# SCH_DINKI-BLINKI_2026-10-03_1.net
KiCad netlist of a schematic drawn in EasyEDA
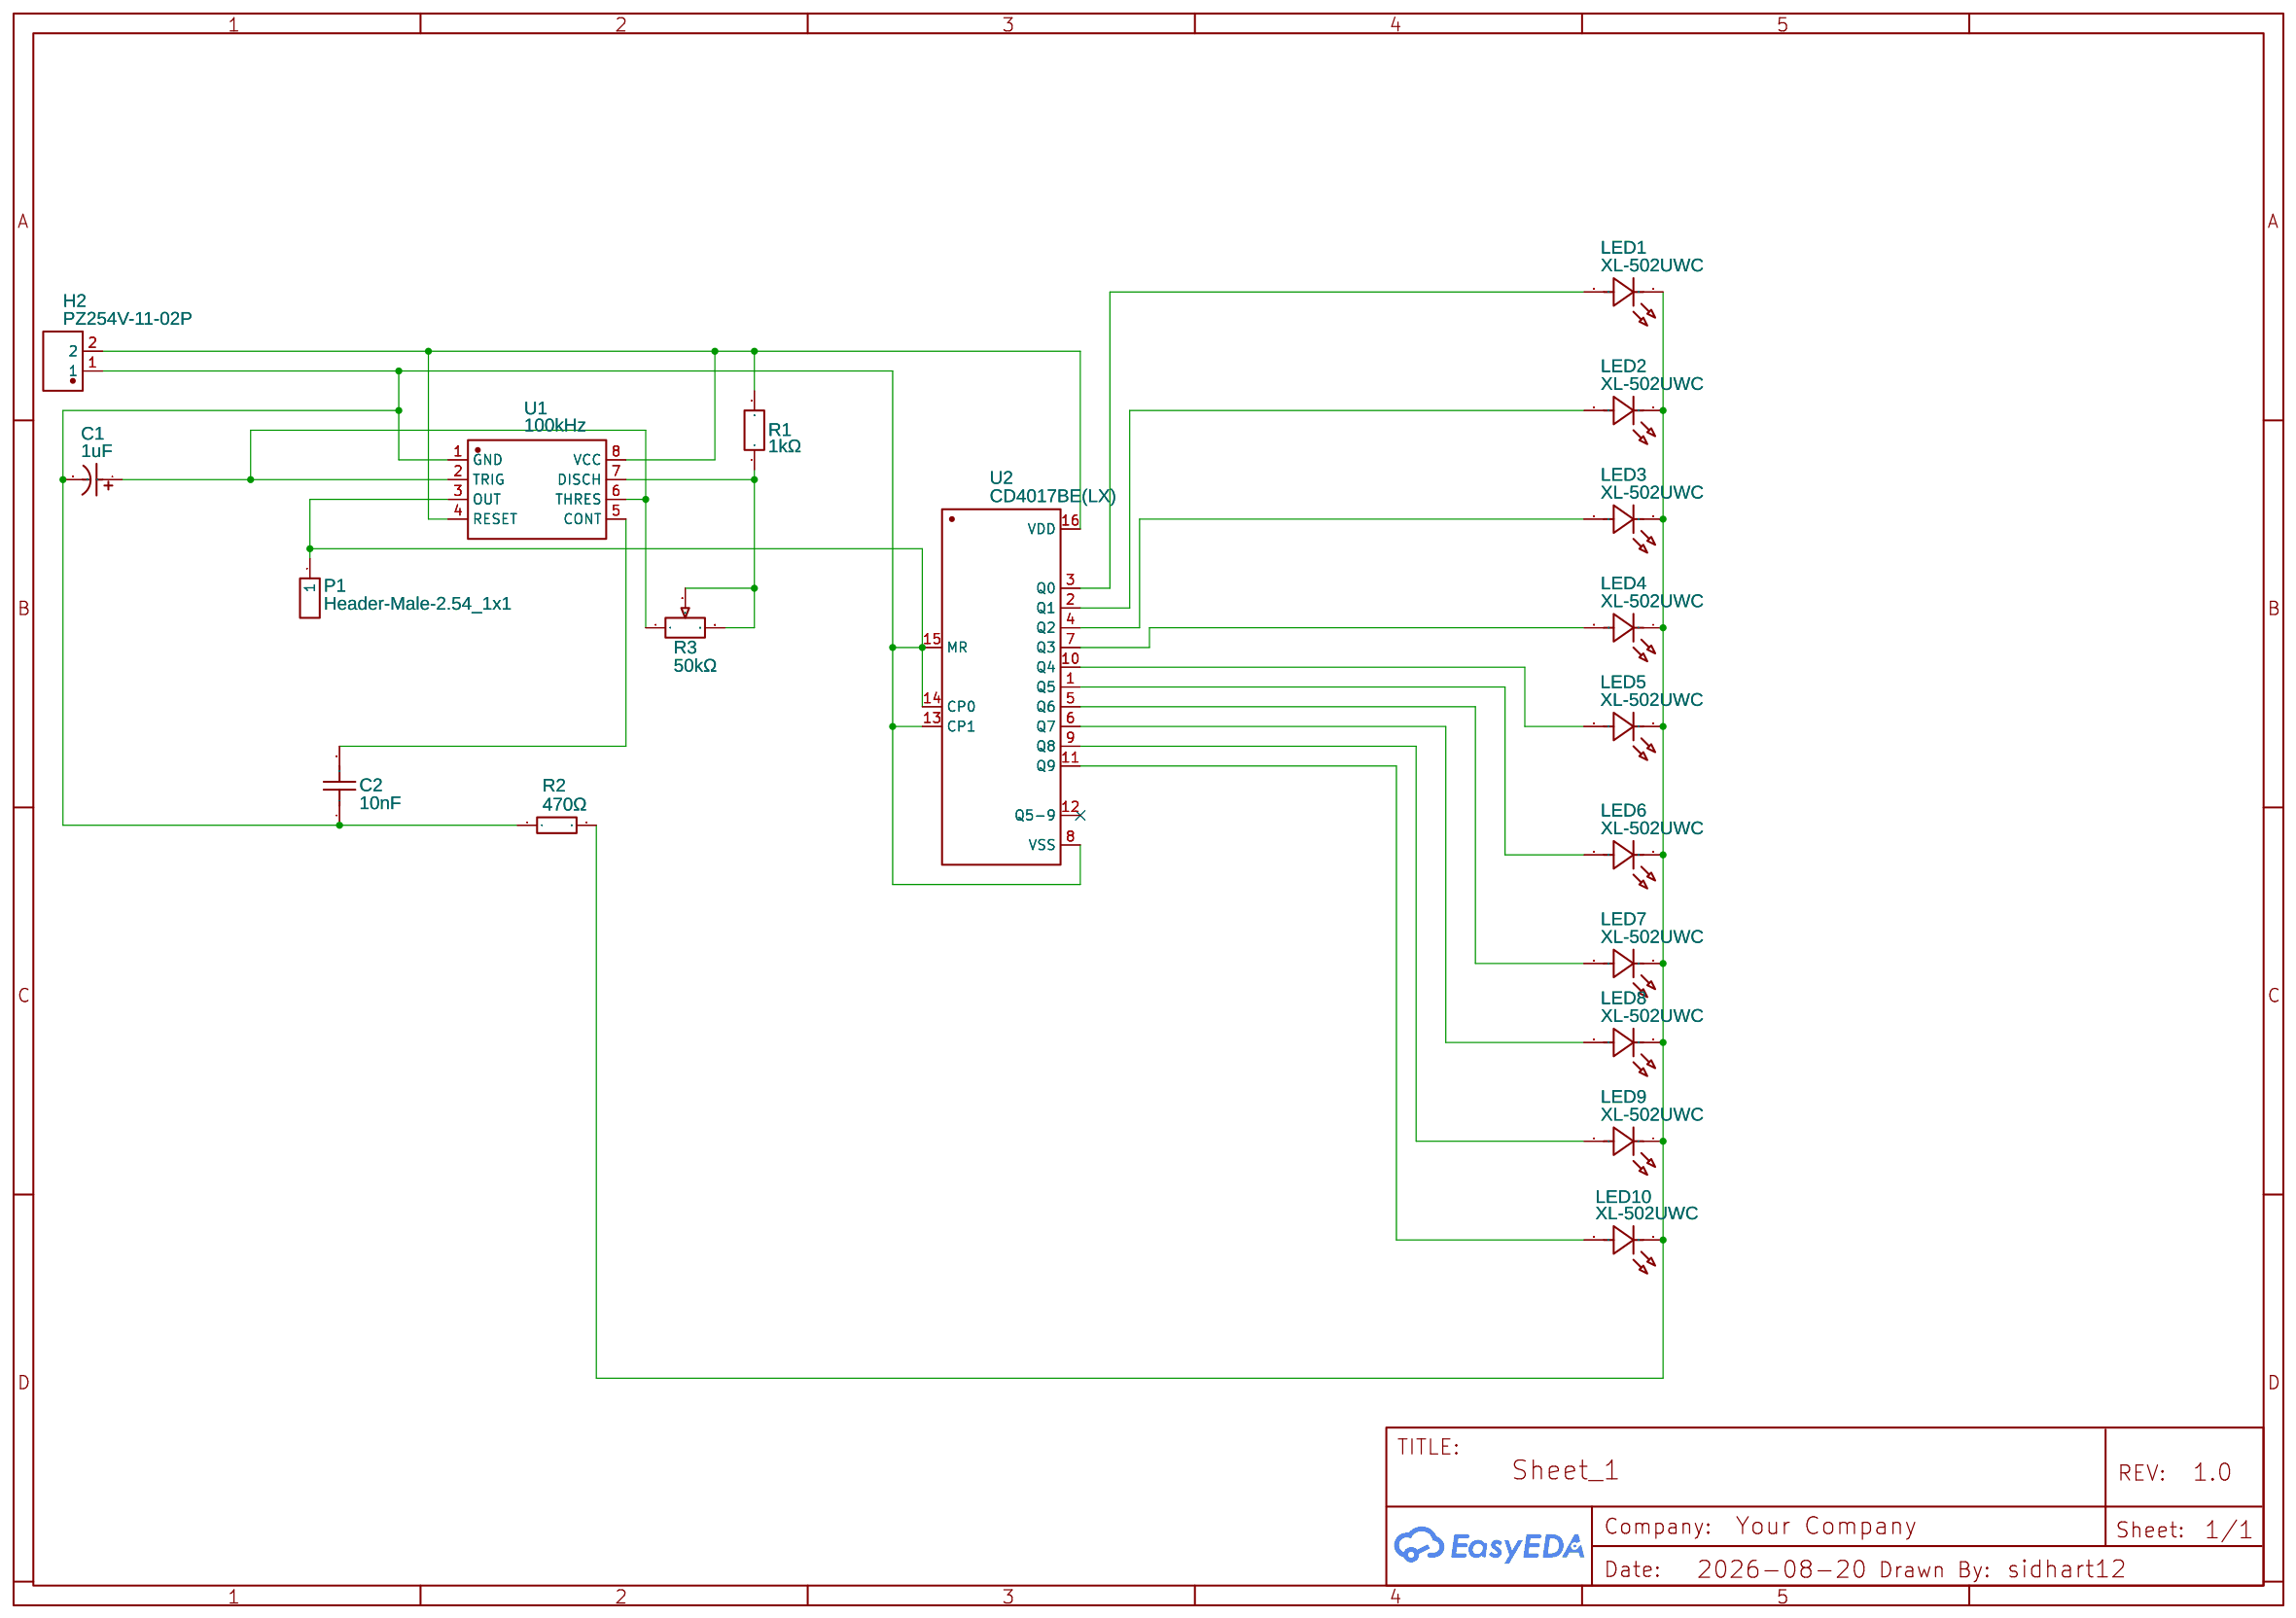
[diagram p0: schematic sheet]

(export (version "E")
  (design (tool "Eeschema 10.0.6"))
  (components
    (comp (ref "C1")
      (value "1uF")
      (fields (field (name "Manufacturer Part") "KF010M050C110A") (field (name "Manufacturer") "CapXon(丰宾)"))
      (libsource (lib "") (part "KF010M050C110A"))
    )
    (comp (ref "C2")
      (value "10nF")
      (fields (field (name "Manufacturer Part") "N09F1B103MN0B0S0N0") (field (name "Manufacturer") "STE(松田)"))
      (libsource (lib "") (part "N09F1B103MN0B0S0N0"))
    )
    (comp (ref "H2")
      (value "PZ254V-11-02P")
      (fields (field (name "Manufacturer") "XFCN(兴飞)"))
      (libsource (lib "") (part "PZ254V-11-02P"))
    )
    (comp (ref "LED1")
      (value "XL-502UWC")
      (fields (field (name "Manufacturer") "XINGLIGHT(成兴光)"))
      (libsource (lib "") (part "XL-502UWC"))
    )
    (comp (ref "LED2")
      (value "XL-502UWC")
      (fields (field (name "Manufacturer") "XINGLIGHT(成兴光)"))
      (libsource (lib "") (part "XL-502UWC"))
    )
    (comp (ref "LED3")
      (value "XL-502UWC")
      (fields (field (name "Manufacturer") "XINGLIGHT(成兴光)"))
      (libsource (lib "") (part "XL-502UWC"))
    )
    (comp (ref "LED4")
      (value "XL-502UWC")
      (fields (field (name "Manufacturer") "XINGLIGHT(成兴光)"))
      (libsource (lib "") (part "XL-502UWC"))
    )
    (comp (ref "LED5")
      (value "XL-502UWC")
      (fields (field (name "Manufacturer") "XINGLIGHT(成兴光)"))
      (libsource (lib "") (part "XL-502UWC"))
    )
    (comp (ref "LED6")
      (value "XL-502UWC")
      (fields (field (name "Manufacturer") "XINGLIGHT(成兴光)"))
      (libsource (lib "") (part "XL-502UWC"))
    )
    (comp (ref "LED7")
      (value "XL-502UWC")
      (fields (field (name "Manufacturer") "XINGLIGHT(成兴光)"))
      (libsource (lib "") (part "XL-502UWC"))
    )
    (comp (ref "LED8")
      (value "XL-502UWC")
      (fields (field (name "Manufacturer") "XINGLIGHT(成兴光)"))
      (libsource (lib "") (part "XL-502UWC"))
    )
    (comp (ref "LED9")
      (value "XL-502UWC")
      (fields (field (name "Manufacturer") "XINGLIGHT(成兴光)"))
      (libsource (lib "") (part "XL-502UWC"))
    )
    (comp (ref "LED10")
      (value "XL-502UWC")
      (fields (field (name "Manufacturer") "XINGLIGHT(成兴光)"))
      (libsource (lib "") (part "XL-502UWC"))
    )
    (comp (ref "P1")
      (value "Header-Male-2.54_1x1")
      (fields (field (name "Manufacturer Part") "2.54-1*1P针") (field (name "Manufacturer") "BOOMELE(博穆精密)"))
      (libsource (lib "") (part "Header-Male-2.54_1x1"))
    )
    (comp (ref "R1")
      (value "1kΩ")
      (fields (field (name "Manufacturer Part") "MF1/4W-1KΩ±1%T52") (field (name "Manufacturer") "华星机电"))
      (libsource (lib "") (part "MF1/4W-1KΩ±1%T52"))
    )
    (comp (ref "R2")
      (value "470Ω")
      (fields
        (field (name "Manufacturer Part") "MFR0W4F4700A50")
        (field (name "Manufacturer") "UNI-ROYAL(厚声)")
      )
      (libsource (lib "") (part "MFR0W4F4700A50"))
    )
    (comp (ref "R3")
      (value "50kΩ")
      (fields (field (name "Manufacturer Part") "3296X-1-503") (field (name "Manufacturer") "BOCHEN(博晨)"))
      (libsource (lib "") (part "3296X-1-503_C118912"))
    )
    (comp (ref "U1")
      (value "100kHz")
      (fields (field (name "Manufacturer Part") "NE555P") (field (name "Manufacturer") "TI(德州仪器)"))
      (libsource (lib "") (part "NE555P"))
    )
    (comp (ref "U2")
      (value "CD4017BE(LX)")
      (fields (field (name "Manufacturer") "LX(灵星芯微)"))
      (libsource (lib "") (part "CD4017BE(LX)"))
    )
  )
  (nets
    (net (code "1") (name "Net-(LED1-A)") (class "Default")
      (node (ref "LED1") (pin "2") (pinfunction "A_2") (pintype "unspecified"))
      (node (ref "U2") (pin "3") (pinfunction "Q0_3") (pintype "unspecified"))
    )
    (net (code "2") (name "Net-(LED1-K)") (class "Default")
      (node (ref "LED1") (pin "1") (pinfunction "K_1") (pintype "unspecified"))
      (node (ref "LED10") (pin "1") (pinfunction "K_1") (pintype "unspecified"))
      (node (ref "LED2") (pin "1") (pinfunction "K_1") (pintype "unspecified"))
      (node (ref "LED3") (pin "1") (pinfunction "K_1") (pintype "unspecified"))
      (node (ref "LED4") (pin "1") (pinfunction "K_1") (pintype "unspecified"))
      (node (ref "LED5") (pin "1") (pinfunction "K_1") (pintype "unspecified"))
      (node (ref "LED6") (pin "1") (pinfunction "K_1") (pintype "unspecified"))
      (node (ref "LED7") (pin "1") (pinfunction "K_1") (pintype "unspecified"))
      (node (ref "LED8") (pin "1") (pinfunction "K_1") (pintype "unspecified"))
      (node (ref "LED9") (pin "1") (pinfunction "K_1") (pintype "unspecified"))
      (node (ref "R2") (pin "2") (pinfunction "2_2") (pintype "input"))
    )
    (net (code "3") (name "Net-(LED2-A)") (class "Default")
      (node (ref "LED2") (pin "2") (pinfunction "A_2") (pintype "unspecified"))
      (node (ref "U2") (pin "2") (pinfunction "Q1_2") (pintype "unspecified"))
    )
    (net (code "4") (name "Net-(LED3-A)") (class "Default")
      (node (ref "LED3") (pin "2") (pinfunction "A_2") (pintype "unspecified"))
      (node (ref "U2") (pin "4") (pinfunction "Q2_4") (pintype "unspecified"))
    )
    (net (code "5") (name "Net-(LED4-A)") (class "Default")
      (node (ref "LED4") (pin "2") (pinfunction "A_2") (pintype "unspecified"))
      (node (ref "U2") (pin "7") (pinfunction "Q3_7") (pintype "unspecified"))
    )
    (net (code "6") (name "Net-(LED5-A)") (class "Default")
      (node (ref "LED5") (pin "2") (pinfunction "A_2") (pintype "unspecified"))
      (node (ref "U2") (pin "10") (pinfunction "Q4_10") (pintype "unspecified"))
    )
    (net (code "7") (name "Net-(LED6-A)") (class "Default")
      (node (ref "LED6") (pin "2") (pinfunction "A_2") (pintype "unspecified"))
      (node (ref "U2") (pin "1") (pinfunction "Q5_1") (pintype "unspecified"))
    )
    (net (code "8") (name "Net-(LED7-A)") (class "Default")
      (node (ref "LED7") (pin "2") (pinfunction "A_2") (pintype "unspecified"))
      (node (ref "U2") (pin "5") (pinfunction "Q6_5") (pintype "unspecified"))
    )
    (net (code "9") (name "Net-(LED8-A)") (class "Default")
      (node (ref "LED8") (pin "2") (pinfunction "A_2") (pintype "unspecified"))
      (node (ref "U2") (pin "6") (pinfunction "Q7_6") (pintype "unspecified"))
    )
    (net (code "10") (name "Net-(LED9-A)") (class "Default")
      (node (ref "LED9") (pin "2") (pinfunction "A_2") (pintype "unspecified"))
      (node (ref "U2") (pin "9") (pinfunction "Q8_9") (pintype "unspecified"))
    )
    (net (code "11") (name "Net-(LED10-A)") (class "Default")
      (node (ref "LED10") (pin "2") (pinfunction "A_2") (pintype "unspecified"))
      (node (ref "U2") (pin "11") (pinfunction "Q9_11") (pintype "unspecified"))
    )
    (net (code "12") (name "Net-(U1-CONT)") (class "Default")
      (node (ref "C2") (pin "2") (pinfunction "2_2") (pintype "unspecified"))
      (node (ref "U1") (pin "5") (pinfunction "CONT_5") (pintype "unspecified"))
    )
    (net (code "13") (name "Net-(U1-DISCH)") (class "Default")
      (node (ref "R1") (pin "1") (pinfunction "1_1") (pintype "unspecified"))
      (node (ref "R3") (pin "2") (pinfunction "2_2") (pintype "input"))
      (node (ref "R3") (pin "3") (pinfunction "3_3") (pintype "input"))
      (node (ref "U1") (pin "7") (pinfunction "DISCH_7") (pintype "unspecified"))
    )
    (net (code "14") (name "Net-(U1-GND)") (class "Default")
      (node (ref "C1") (pin "2") (pinfunction "2_2") (pintype "input"))
      (node (ref "C2") (pin "1") (pinfunction "1_1") (pintype "unspecified"))
      (node (ref "H2") (pin "1") (pinfunction "1_1") (pintype "unspecified"))
      (node (ref "P1") (pin "1") (pinfunction "1_1") (pintype "input"))
      (node (ref "R2") (pin "1") (pinfunction "1_1") (pintype "input"))
      (node (ref "U1") (pin "1") (pinfunction "GND_1") (pintype "unspecified"))
      (node (ref "U1") (pin "3") (pinfunction "OUT_3") (pintype "unspecified"))
      (node (ref "U2") (pin "13") (pinfunction "CP1_13") (pintype "unspecified"))
      (node (ref "U2") (pin "14") (pinfunction "CP0_14") (pintype "unspecified"))
      (node (ref "U2") (pin "15") (pinfunction "MR_15") (pintype "unspecified"))
      (node (ref "U2") (pin "8") (pinfunction "VSS_8") (pintype "unspecified"))
    )
    (net (code "15") (name "Net-(U1-RESET)") (class "Default")
      (node (ref "H2") (pin "2") (pinfunction "2_2") (pintype "unspecified"))
      (node (ref "R1") (pin "2") (pinfunction "2_2") (pintype "unspecified"))
      (node (ref "U1") (pin "4") (pinfunction "RESET_4") (pintype "unspecified"))
      (node (ref "U1") (pin "8") (pinfunction "VCC_8") (pintype "unspecified"))
      (node (ref "U2") (pin "16") (pinfunction "VDD_16") (pintype "unspecified"))
    )
    (net (code "16") (name "Net-(U1-THRES)") (class "Default")
      (node (ref "C1") (pin "1") (pinfunction "1_1") (pintype "input"))
      (node (ref "R3") (pin "1") (pinfunction "1_1") (pintype "input"))
      (node (ref "U1") (pin "2") (pinfunction "TRIG_2") (pintype "unspecified"))
      (node (ref "U1") (pin "6") (pinfunction "THRES_6") (pintype "unspecified"))
    )
    (net (code "17") (name "unconnected-(U2-Q5-9-Pad12)") (class "Default")
      (node (ref "U2") (pin "12") (pinfunction "Q5-9_12") (pintype "unspecified+no_connect"))
    )
  )
)
